# PowerRegulationBoard.net
KiCad netlist of a schematic drawn in Altium Designer
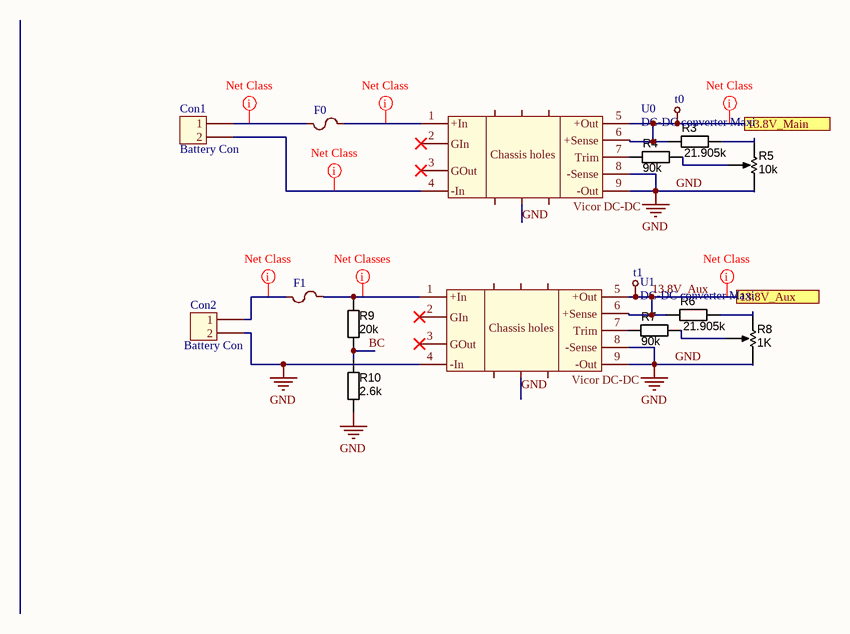
[diagram p0: PowerRegulationBoard.SchDoc]

(export (version "E")
  (design (tool "Eeschema 10.0.6"))
  (components
    (comp (ref "Con1")
      (value "Battery Con")
      (footprint "Battery Con")
      (description "Aux and Main battery connector")
      (libsource (lib "Components_library") (part "Battery Con"))
    )
    (comp (ref "Con2")
      (value "Battery Con")
      (footprint "Battery Con")
      (description "Aux and Main battery connector")
      (libsource (lib "Components_library") (part "Battery Con"))
    )
    (comp (ref "F0")
      (value "PC TRON Fuse 5A")
      (footprint "PC TRON 5A")
      (libsource (lib "Components_library") (part "PC TRON Fuse 5A"))
    )
    (comp (ref "F1")
      (value "10A/32VDC Fuse holder")
      (footprint "10A/32V Fuse")
      (libsource (lib "Components_library") (part "10A/32VDC Fuse holder"))
    )
    (comp (ref "R3")
      (value "21.905k")
      (footprint "RESC5025X70N")
      (description "Resistor SMD chip 10 Ohm 0.25W 5% 2010")
      (fields (field (name "TOLERANCE") "±5%") (field (name "Comment") "Thick Film"))
      (libsource (lib "PBL - Resistors") (part "RES_10R_2010_5%"))
    )
    (comp (ref "R4")
      (value "90k")
      (footprint "RESC5025X70N")
      (description "Resistor SMD chip 10 Ohm 0.25W 5% 2010")
      (fields (field (name "TOLERANCE") "±5%") (field (name "Comment") "Thick Film"))
      (libsource (lib "PBL - Resistors") (part "RES_10R_2010_5%"))
    )
    (comp (ref "R5")
      (value "10k")
      (footprint "TrimPot_THT_2.54mm pitch")
      (description "Trimmer, 25-Turn, 1K cermet")
      (fields (field (name "TOLERANCE") "10%") (field (name "Comment") "25 Turn"))
      (libsource (lib "PBL - Resistors") (part "RES_TRIMMER_1K_25T_THT"))
    )
    (comp (ref "R6")
      (value "21.905k")
      (footprint "RESC5025X70N")
      (description "Resistor SMD chip 10 Ohm 0.25W 5% 2010")
      (fields (field (name "TOLERANCE") "±5%") (field (name "Comment") "Thick Film"))
      (libsource (lib "PBL - Resistors") (part "RES_10R_2010_5%"))
    )
    (comp (ref "R7")
      (value "90k")
      (footprint "RESC5025X70N")
      (description "Resistor SMD chip 10 Ohm 0.25W 5% 2010")
      (fields (field (name "TOLERANCE") "±5%") (field (name "Comment") "Thick Film"))
      (libsource (lib "PBL - Resistors") (part "RES_10R_2010_5%"))
    )
    (comp (ref "R8")
      (value "1K")
      (footprint "TrimPot_THT_2.54mm pitch")
      (description "Trimmer, 25-Turn, 1K cermet")
      (fields (field (name "TOLERANCE") "10%") (field (name "Comment") "25 Turn"))
      (libsource (lib "PBL - Resistors") (part "RES_TRIMMER_1K_25T_THT"))
    )
    (comp (ref "R9")
      (value "20k")
      (footprint "RESC5025X70N")
      (description "Resistor SMD chip 10 Ohm 0.25W 5% 2010")
      (fields (field (name "TOLERANCE") "±5%") (field (name "Comment") "Thick Film"))
      (libsource (lib "") (part "RES_10R_2010_5%_1"))
    )
    (comp (ref "R10")
      (value "2.6k")
      (footprint "RESC5025X70N")
      (description "Resistor SMD chip 10 Ohm 0.25W 5% 2010")
      (fields (field (name "TOLERANCE") "±5%") (field (name "Comment") "Thick Film"))
      (libsource (lib "") (part "RES_10R_2010_5%_1"))
    )
    (comp (ref "t0")
      (value "Testpoint")
      (footprint "TestPoint")
      (libsource (lib "Components_library") (part "Testpoint"))
    )
    (comp (ref "t1")
      (value "Testpoint")
      (footprint "TestPoint")
      (libsource (lib "Components_library") (part "Testpoint"))
    )
    (comp (ref "U0")
      (value "DC-DC converter Maxi")
      (footprint "Vicor DC-DC Maxi")
      (libsource (lib "Components_library") (part "DC-DC converter Maxi"))
    )
    (comp (ref "U1")
      (value "DC-DC converter Maxi")
      (footprint "Vicor DC-DC Maxi")
      (libsource (lib "Components_library") (part "DC-DC converter Maxi"))
    )
  )
  (nets
    (net (code "1") (name "/13.8V_Aux") (class "Default")
      (node (ref "R6") (pin "2") (pinfunction "2_2") (pintype "passive"))
      (node (ref "U1") (pin "5") (pinfunction "+Out_5") (pintype "power_in"))
      (node (ref "U1") (pin "6") (pinfunction "+Sense_6") (pintype "power_in"))
      (node (ref "t1") (pin "1") (pinfunction "1_1") (pintype "passive"))
    )
    (net (code "2") (name "/13.8V_Main") (class "Default")
      (node (ref "R3") (pin "2") (pinfunction "2_2") (pintype "passive"))
      (node (ref "U0") (pin "5") (pinfunction "+Out_5") (pintype "power_in"))
      (node (ref "U0") (pin "6") (pinfunction "+Sense_6") (pintype "power_in"))
      (node (ref "t0") (pin "1") (pinfunction "1_1") (pintype "passive"))
    )
    (net (code "3") (name "/BC") (class "Default")
      (node (ref "R10") (pin "2") (pinfunction "2_2") (pintype "passive"))
      (node (ref "R9") (pin "1") (pinfunction "1_1") (pintype "passive"))
    )
    (net (code "4") (name "GND") (class "Default")
      (node (ref "Con2") (pin "2") (pinfunction "2_2") (pintype "passive"))
      (node (ref "R10") (pin "1") (pinfunction "1_1") (pintype "passive"))
      (node (ref "R5") (pin "3") (pinfunction "CW_3") (pintype "passive"))
      (node (ref "R8") (pin "3") (pinfunction "CW_3") (pintype "passive"))
      (node (ref "U0") (pin "12") (pinfunction "12_12") (pintype "passive"))
      (node (ref "U0") (pin "8") (pinfunction "-Sense_8") (pintype "power_in"))
      (node (ref "U0") (pin "9") (pinfunction "-Out_9") (pintype "power_in"))
      (node (ref "U1") (pin "12") (pinfunction "12_12") (pintype "passive"))
      (node (ref "U1") (pin "4") (pinfunction "-In_4") (pintype "power_in"))
      (node (ref "U1") (pin "8") (pinfunction "-Sense_8") (pintype "power_in"))
      (node (ref "U1") (pin "9") (pinfunction "-Out_9") (pintype "power_in"))
    )
    (net (code "5") (name "Net-(Con1-Pad1)") (class "Default")
      (node (ref "Con1") (pin "1") (pinfunction "1_1") (pintype "passive"))
      (node (ref "F0") (pin "1") (pinfunction "1_1") (pintype "passive"))
    )
    (net (code "6") (name "Net-(Con2-Pad1)") (class "Default")
      (node (ref "Con2") (pin "1") (pinfunction "1_1") (pintype "passive"))
      (node (ref "F1") (pin "1") (pinfunction "1_1") (pintype "passive"))
    )
    (net (code "7") (name "Net-(R5-CCW)") (class "Default")
      (node (ref "R3") (pin "1") (pinfunction "1_1") (pintype "passive"))
      (node (ref "R5") (pin "1") (pinfunction "CCW_1") (pintype "passive"))
    )
    (net (code "8") (name "Net-(R5-TAP)") (class "Default")
      (node (ref "R4") (pin "1") (pinfunction "1_1") (pintype "passive"))
      (node (ref "R5") (pin "2") (pinfunction "TAP_2") (pintype "passive"))
    )
    (net (code "9") (name "Net-(R8-CCW)") (class "Default")
      (node (ref "R6") (pin "1") (pinfunction "1_1") (pintype "passive"))
      (node (ref "R8") (pin "1") (pinfunction "CCW_1") (pintype "passive"))
    )
    (net (code "10") (name "Net-(R8-TAP)") (class "Default")
      (node (ref "R7") (pin "1") (pinfunction "1_1") (pintype "passive"))
      (node (ref "R8") (pin "2") (pinfunction "TAP_2") (pintype "passive"))
    )
    (net (code "11") (name "Net-(U0-+In)") (class "Default")
      (node (ref "F0") (pin "2") (pinfunction "2_2") (pintype "passive"))
      (node (ref "U0") (pin "1") (pinfunction "+In_1") (pintype "power_in"))
    )
    (net (code "12") (name "Net-(U0--In)") (class "Default")
      (node (ref "Con1") (pin "2") (pinfunction "2_2") (pintype "passive"))
      (node (ref "U0") (pin "4") (pinfunction "-In_4") (pintype "power_in"))
    )
    (net (code "13") (name "Net-(U0-Trim)") (class "Default")
      (node (ref "R4") (pin "2") (pinfunction "2_2") (pintype "passive"))
      (node (ref "U0") (pin "7") (pinfunction "Trim_7") (pintype "power_in"))
    )
    (net (code "14") (name "Net-(U1-+In)") (class "Default")
      (node (ref "F1") (pin "2") (pinfunction "2_2") (pintype "passive"))
      (node (ref "R9") (pin "2") (pinfunction "2_2") (pintype "passive"))
      (node (ref "U1") (pin "1") (pinfunction "+In_1") (pintype "power_in"))
    )
    (net (code "15") (name "Net-(U1-Trim)") (class "Default")
      (node (ref "R7") (pin "2") (pinfunction "2_2") (pintype "passive"))
      (node (ref "U1") (pin "7") (pinfunction "Trim_7") (pintype "power_in"))
    )
    (net (code "16") (name "unconnected-(U0-10-Pad11)") (class "Default")
      (node (ref "U0") (pin "11") (pinfunction "10_11") (pintype "passive"))
    )
    (net (code "17") (name "unconnected-(U0-GIn-Pad2)") (class "Default")
      (node (ref "U0") (pin "2") (pinfunction "GIn_2") (pintype "power_in+no_connect"))
    )
    (net (code "18") (name "unconnected-(U0-GOut-Pad3)") (class "Default")
      (node (ref "U0") (pin "3") (pinfunction "GOut_3") (pintype "power_in+no_connect"))
    )
    (net (code "19") (name "unconnected-(U0-Pad11)") (class "Default")
      (node (ref "U0") (pin "11") (pinfunction "11_11") (pintype "passive"))
    )
    (net (code "20") (name "unconnected-(U0-Pad13)") (class "Default")
      (node (ref "U0") (pin "13") (pinfunction "13_13") (pintype "passive"))
    )
    (net (code "21") (name "unconnected-(U0-Pad14)") (class "Default")
      (node (ref "U0") (pin "14") (pinfunction "14_14") (pintype "passive"))
    )
    (net (code "22") (name "unconnected-(U0-Pad15)") (class "Default")
      (node (ref "U0") (pin "15") (pinfunction "15_15") (pintype "passive"))
    )
    (net (code "23") (name "unconnected-(U1-10-Pad11)") (class "Default")
      (node (ref "U1") (pin "11") (pinfunction "10_11") (pintype "passive"))
    )
    (net (code "24") (name "unconnected-(U1-GIn-Pad2)") (class "Default")
      (node (ref "U1") (pin "2") (pinfunction "GIn_2") (pintype "power_in+no_connect"))
    )
    (net (code "25") (name "unconnected-(U1-GOut-Pad3)") (class "Default")
      (node (ref "U1") (pin "3") (pinfunction "GOut_3") (pintype "power_in+no_connect"))
    )
    (net (code "26") (name "unconnected-(U1-Pad11)") (class "Default")
      (node (ref "U1") (pin "11") (pinfunction "11_11") (pintype "passive"))
    )
    (net (code "27") (name "unconnected-(U1-Pad13)") (class "Default")
      (node (ref "U1") (pin "13") (pinfunction "13_13") (pintype "passive"))
    )
    (net (code "28") (name "unconnected-(U1-Pad14)") (class "Default")
      (node (ref "U1") (pin "14") (pinfunction "14_14") (pintype "passive"))
    )
    (net (code "29") (name "unconnected-(U1-Pad15)") (class "Default")
      (node (ref "U1") (pin "15") (pinfunction "15_15") (pintype "passive"))
    )
  )
)
